# 09_RST_WDT_CAT823.net
KiCad netlist of a schematic drawn in Altium Designer
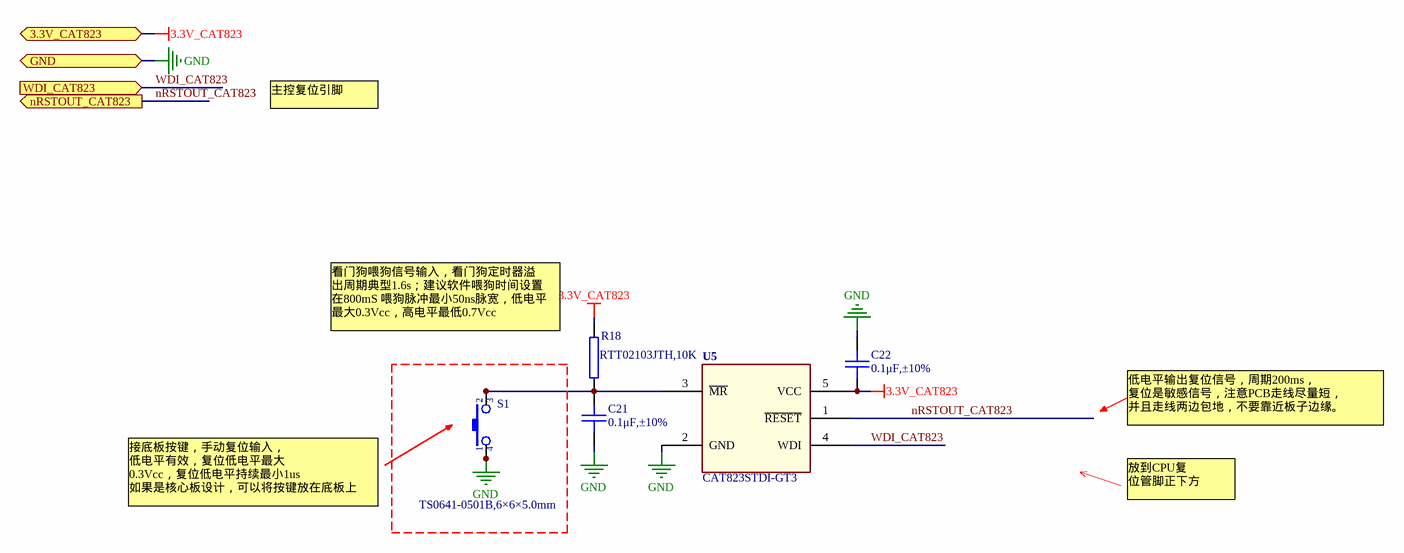
[diagram p0: 09.RST_WDT_CAT823.SchDoc]

(export (version "E")
  (design (tool "Eeschema 10.0.6"))
  (components
    (comp (ref "C21")
      (value "0.1μF,±10%")
      (footprint "0402C")
      (description "GRM155R71C104KA88D,0.1μF,±10%,16V,X7R,0402,muRata,RoHS")
      (libsource (lib "ErpMaterialData") (part "CAP1"))
    )
    (comp (ref "C22")
      (value "0.1μF,±10%")
      (footprint "0402C")
      (description "GRM155R71C104KA88D,0.1μF,±10%,16V,X7R,0402,muRata,RoHS")
      (libsource (lib "ErpMaterialData") (part "CAP1"))
    )
    (comp (ref "R18")
      (value "RTT02103JTH,10K")
      (footprint "0402R")
      (description "RTT02103JTH,10K,±5%,0402,RALEC,RoHS")
      (libsource (lib "ErpMaterialData") (part "RES2"))
    )
    (comp (ref "S1")
      (value "TS0641-0501B,6×6×5.0mm")
      (footprint "KEY-6S")
      (description "TS0641-0501B,6×6×5.0mm,黑色,SMD,卷带装,RoHS")
      (libsource (lib "ErpMaterialData") (part "SW-PB4P"))
    )
    (comp (ref "U5")
      (value "CAT823STDI-GT3")
      (footprint "SOT-23-5")
      (description "1.05.07.0025")
      (libsource (lib "CAT823") (part "CAT823"))
    )
  )
  (nets
    (net (code "1") (name "/WDI_CAT823") (class "Default")
      (node (ref "U5") (pin "4") (pinfunction "WDI_4") (pintype "passive"))
    )
    (net (code "2") (name "/nRSTOUT_CAT823") (class "Default")
      (node (ref "U5") (pin "1") (pinfunction "~{RESET}_1") (pintype "passive"))
    )
    (net (code "3") (name "3.3V_CAT823") (class "Default")
      (node (ref "C22") (pin "2") (pinfunction "2_2") (pintype "passive"))
      (node (ref "R18") (pin "1") (pinfunction "1_1") (pintype "passive"))
      (node (ref "U5") (pin "5") (pinfunction "VCC_5") (pintype "passive"))
    )
    (net (code "4") (name "GND") (class "Default")
      (node (ref "C21") (pin "2") (pinfunction "2_2") (pintype "passive"))
      (node (ref "C22") (pin "1") (pinfunction "1_1") (pintype "passive"))
      (node (ref "S1") (pin "1") (pinfunction "1_1") (pintype "passive"))
      (node (ref "S1") (pin "4") (pinfunction "4_4") (pintype "passive"))
      (node (ref "U5") (pin "2") (pinfunction "GND_2") (pintype "passive"))
    )
    (net (code "5") (name "Net-(U5-~{MR})") (class "Default")
      (node (ref "C21") (pin "1") (pinfunction "1_1") (pintype "passive"))
      (node (ref "R18") (pin "2") (pinfunction "2_2") (pintype "passive"))
      (node (ref "S1") (pin "2") (pinfunction "2_2") (pintype "passive"))
      (node (ref "S1") (pin "3") (pinfunction "3_3") (pintype "passive"))
      (node (ref "U5") (pin "3") (pinfunction "~{MR}_3") (pintype "passive"))
    )
  )
)
